# RotorStator_PowerControl.net
KiCad netlist of a schematic drawn in Altium Designer
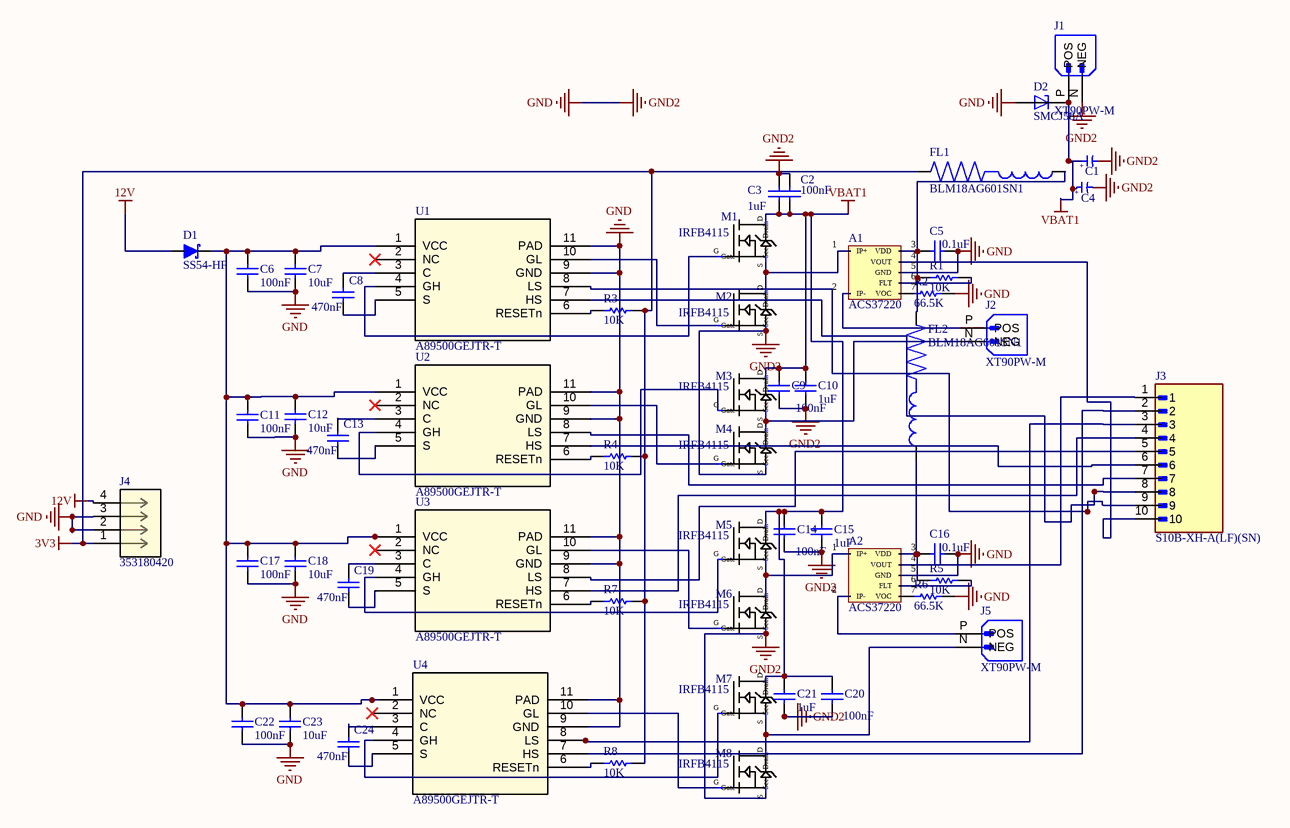
[diagram p0: RotorStator_PowerControl.SchDoc]

(export (version "E")
  (design (tool "Eeschema 10.0.6"))
  (components
    (comp (ref "A1") (value "ACS37220") (footprint "ACS37220") (libsource (lib "Schlib1") (part "ACS37220")))
    (comp (ref "A2") (value "ACS37220") (footprint "ACS37220") (libsource (lib "Schlib1") (part "ACS37220")))
    (comp (ref "C1")
      (value "MAL215099913E3")
      (footprint "CAPAE1900X2200N")
      (description "Cap Aluminum Lytic 470uF 100V 20% (18 X 21mm) SMD 1450mA 5000h 105Â°C Automotive AEC-Q200 T/R")
      (fields (field (name "MF") "Vishay Beyschlag/Draloric"))
      (libsource (lib "") (part "MAL215099913E3_1"))
    )
    (comp (ref "C2")
      (value "100nF")
      (footprint "CAP0805R")
      (description "Capacitor")
      (libsource (lib "Simulation Generic Components") (part "Capacitor"))
    )
    (comp (ref "C3")
      (value "1uF")
      (footprint "CAP0805R")
      (description "Capacitor")
      (libsource (lib "Simulation Generic Components") (part "Capacitor"))
    )
    (comp (ref "C4")
      (value "MAL215099913E3")
      (footprint "CAPAE1900X2200N")
      (description "Cap Aluminum Lytic 470uF 100V 20% (18 X 21mm) SMD 1450mA 5000h 105Â°C Automotive AEC-Q200 T/R")
      (fields (field (name "MF") "Vishay Beyschlag/Draloric"))
      (libsource (lib "Schlib1") (part "MAL215099913E3"))
    )
    (comp (ref "C5")
      (value "0.1uF")
      (footprint "CAP0805R")
      (description "Capacitor")
      (libsource (lib "Simulation Generic Components") (part "Capacitor"))
    )
    (comp (ref "C6")
      (value "100nF")
      (footprint "CAP0805R")
      (description "Capacitor")
      (libsource (lib "Simulation Generic Components") (part "Capacitor"))
    )
    (comp (ref "C7")
      (value "10uF")
      (footprint "CAP0805R")
      (description "Capacitor")
      (libsource (lib "Simulation Generic Components") (part "Capacitor"))
    )
    (comp (ref "C8")
      (value "470nF")
      (footprint "CAP0805R")
      (description "Capacitor")
      (libsource (lib "Simulation Generic Components") (part "Capacitor"))
    )
    (comp (ref "C9")
      (value "100nF")
      (footprint "CAP0805R")
      (description "Capacitor")
      (libsource (lib "Simulation Generic Components") (part "Capacitor"))
    )
    (comp (ref "C10")
      (value "1uF")
      (footprint "CAP0805R")
      (description "Capacitor")
      (libsource (lib "Simulation Generic Components") (part "Capacitor"))
    )
    (comp (ref "C11")
      (value "100nF")
      (footprint "CAP0805R")
      (description "Capacitor")
      (libsource (lib "Simulation Generic Components") (part "Capacitor"))
    )
    (comp (ref "C12")
      (value "10uF")
      (footprint "CAP0805R")
      (description "Capacitor")
      (libsource (lib "Simulation Generic Components") (part "Capacitor"))
    )
    (comp (ref "C13")
      (value "470nF")
      (footprint "CAP0805R")
      (description "Capacitor")
      (libsource (lib "Simulation Generic Components") (part "Capacitor"))
    )
    (comp (ref "C14")
      (value "100nF")
      (footprint "CAP0805R")
      (description "Capacitor")
      (libsource (lib "Simulation Generic Components") (part "Capacitor"))
    )
    (comp (ref "C15")
      (value "1uF")
      (footprint "CAP0805R")
      (description "Capacitor")
      (libsource (lib "Simulation Generic Components") (part "Capacitor"))
    )
    (comp (ref "C16")
      (value "0.1uF")
      (footprint "CAP0805R")
      (description "Capacitor")
      (libsource (lib "Simulation Generic Components") (part "Capacitor"))
    )
    (comp (ref "C17")
      (value "100nF")
      (footprint "CAP0805R")
      (description "Capacitor")
      (libsource (lib "Simulation Generic Components") (part "Capacitor"))
    )
    (comp (ref "C18")
      (value "10uF")
      (footprint "CAP0805R")
      (description "Capacitor")
      (libsource (lib "Simulation Generic Components") (part "Capacitor"))
    )
    (comp (ref "C19")
      (value "470nF")
      (footprint "CAP0805R")
      (description "Capacitor")
      (libsource (lib "Simulation Generic Components") (part "Capacitor"))
    )
    (comp (ref "C20")
      (value "100nF")
      (footprint "CAP0805R")
      (description "Capacitor")
      (libsource (lib "Simulation Generic Components") (part "Capacitor"))
    )
    (comp (ref "C21")
      (value "1uF")
      (footprint "CAP0805R")
      (description "Capacitor")
      (libsource (lib "Simulation Generic Components") (part "Capacitor"))
    )
    (comp (ref "C22")
      (value "100nF")
      (footprint "CAP0805R")
      (description "Capacitor")
      (libsource (lib "Simulation Generic Components") (part "Capacitor"))
    )
    (comp (ref "C23")
      (value "10uF")
      (footprint "CAP0805R")
      (description "Capacitor")
      (libsource (lib "Simulation Generic Components") (part "Capacitor"))
    )
    (comp (ref "C24")
      (value "470nF")
      (footprint "CAP0805R")
      (description "Capacitor")
      (libsource (lib "Simulation Generic Components") (part "Capacitor"))
    )
    (comp (ref "D1")
      (value "SS54-HF")
      (footprint "DIOM5025X220N")
      (description "Diode Schottky 40 V 5A Surface Mount DO-214AC (SMA)")
      (fields (field (name "MF") "Comchip Technology"))
      (libsource (lib "Schlib1") (part "SS54-HF"))
    )
    (comp (ref "D2")
      (value "SMCJ58A")
      (footprint "DIOM7959X262N")
      (description "93.6V Clamp 16.1A Ipp Tvs Diode Surface Mount DO-214AB (SMC)")
      (fields (field (name "MF") "Fairchild Semiconductor"))
      (libsource (lib "Schlib1") (part "SMCJ58A"))
    )
    (comp (ref "FL1")
      (value "BLM18AG601SN1")
      (footprint "BEADC1608X95N")
      (description "600 Ohms @ 100 MHz 1 - Ferrite Bead 0603 (1608 Metric) 500mA 380mOhm")
      (fields (field (name "MF") "Murata Electronics"))
      (libsource (lib "Schlib1") (part "BLM18AG601SN1"))
    )
    (comp (ref "FL2")
      (value "BLM18AG601SN1")
      (footprint "BEADC1608X95N")
      (description "600 Ohms @ 100 MHz 1 - Ferrite Bead 0603 (1608 Metric) 500mA 380mOhm")
      (fields (field (name "MF") "Murata Electronics"))
      (libsource (lib "Schlib1") (part "BLM18AG601SN1"))
    )
    (comp (ref "J1")
      (value "XT90PW-M")
      (footprint "AMASS_XT90PW-M")
      (description "Socket; DC supply; XT90; male; PIN: 2; on PCBs; THT; Colour: yellow")
      (fields (field (name "MF") "AMASS"))
      (libsource (lib "") (part "XT90PW-M_1"))
    )
    (comp (ref "J2")
      (value "XT90PW-M")
      (footprint "AMASS_XT90PW-M")
      (description "Socket; DC supply; XT90; male; PIN: 2; on PCBs; THT; Colour: yellow")
      (fields (field (name "MF") "AMASS"))
      (libsource (lib "Schlib1") (part "XT90PW-M"))
    )
    (comp (ref "J3")
      (value "S10B-XH-A(LF)(SN)")
      (footprint "JST_S10B-XH-A(LF)(SN)")
      (libsource (lib "Schlib1") (part "S10B-XH-A(LF)(SN)"))
    )
    (comp (ref "J4")
      (value "353180420")
      (footprint "MOLEX_353180420")
      (description "Connector Header Through Hole, Right Angle 4 position 0.165in (4.20mm)")
      (libsource (lib "Schlib1") (part "353180420"))
    )
    (comp (ref "J5")
      (value "XT90PW-M")
      (footprint "AMASS_XT90PW-M")
      (description "Socket; DC supply; XT90; male; PIN: 2; on PCBs; THT; Colour: yellow")
      (fields (field (name "MF") "AMASS"))
      (libsource (lib "Schlib1") (part "XT90PW-M"))
    )
    (comp (ref "M1") (value "IRFB4115") (footprint "IRFB4115") (libsource (lib "Schlib1") (part "IRFB4115")))
    (comp (ref "M2") (value "IRFB4115") (footprint "IRFB4115") (libsource (lib "Schlib1") (part "IRFB4115")))
    (comp (ref "M3") (value "IRFB4115") (footprint "IRFB4115") (libsource (lib "Schlib1") (part "IRFB4115")))
    (comp (ref "M4") (value "IRFB4115") (footprint "IRFB4115") (libsource (lib "Schlib1") (part "IRFB4115")))
    (comp (ref "M5") (value "IRFB4115") (footprint "IRFB4115") (libsource (lib "Schlib1") (part "IRFB4115")))
    (comp (ref "M6") (value "IRFB4115") (footprint "IRFB4115") (libsource (lib "Schlib1") (part "IRFB4115")))
    (comp (ref "M7") (value "IRFB4115") (footprint "IRFB4115") (libsource (lib "Schlib1") (part "IRFB4115")))
    (comp (ref "M8") (value "IRFB4115") (footprint "IRFB4115") (libsource (lib "Schlib1") (part "IRFB4115")))
    (comp (ref "R1")
      (value "10K")
      (footprint "RES0805W")
      (description "Resistor")
      (libsource (lib "Simulation Generic Components") (part "Resistor"))
    )
    (comp (ref "R2")
      (value "66.5K")
      (footprint "RES0805W")
      (description "Resistor")
      (libsource (lib "Simulation Generic Components") (part "Resistor"))
    )
    (comp (ref "R3")
      (value "10K")
      (footprint "RES0805W")
      (description "Resistor")
      (libsource (lib "Simulation Generic Components") (part "Resistor"))
    )
    (comp (ref "R4")
      (value "10K")
      (footprint "RES0805W")
      (description "Resistor")
      (libsource (lib "Simulation Generic Components") (part "Resistor"))
    )
    (comp (ref "R5")
      (value "10K")
      (footprint "RES0805W")
      (description "Resistor")
      (libsource (lib "Simulation Generic Components") (part "Resistor"))
    )
    (comp (ref "R6")
      (value "66.5K")
      (footprint "RES0805W")
      (description "Resistor")
      (libsource (lib "Simulation Generic Components") (part "Resistor"))
    )
    (comp (ref "R7")
      (value "10K")
      (footprint "RES0805W")
      (description "Resistor")
      (libsource (lib "Simulation Generic Components") (part "Resistor"))
    )
    (comp (ref "R8")
      (value "10K")
      (footprint "RES0805W")
      (description "Resistor")
      (libsource (lib "Simulation Generic Components") (part "Resistor"))
    )
    (comp (ref "U1")
      (value "A89500GEJTR-T")
      (footprint "A89500GEJTR-T")
      (description "Description")
      (fields (field (name "COPYRIGHT") "Copyright (C) 2025 Ultra Librarian. All rights reserved."))
      (libsource (lib "Schlib1") (part "A89500GEJTR-T"))
    )
    (comp (ref "U2")
      (value "A89500GEJTR-T")
      (footprint "A89500GEJTR-T")
      (description "Description")
      (fields (field (name "COPYRIGHT") "Copyright (C) 2025 Ultra Librarian. All rights reserved."))
      (libsource (lib "Schlib1") (part "A89500GEJTR-T"))
    )
    (comp (ref "U3")
      (value "A89500GEJTR-T")
      (footprint "A89500GEJTR-T")
      (description "Description")
      (fields (field (name "COPYRIGHT") "Copyright (C) 2025 Ultra Librarian. All rights reserved."))
      (libsource (lib "Schlib1") (part "A89500GEJTR-T"))
    )
    (comp (ref "U4")
      (value "A89500GEJTR-T")
      (footprint "A89500GEJTR-T")
      (description "Description")
      (fields (field (name "COPYRIGHT") "Copyright (C) 2025 Ultra Librarian. All rights reserved."))
      (libsource (lib "Schlib1") (part "A89500GEJTR-T"))
    )
  )
  (nets
    (net (code "1") (name "3V3") (class "Default")
      (node (ref "FL1") (pin "2") (pinfunction "2_2") (pintype "passive"))
      (node (ref "J4") (pin "1") (pinfunction "1_1") (pintype "passive"))
      (node (ref "R3") (pin "1") (pinfunction "1_1") (pintype "passive"))
      (node (ref "R4") (pin "1") (pinfunction "1_1") (pintype "passive"))
      (node (ref "R7") (pin "1") (pinfunction "1_1") (pintype "passive"))
      (node (ref "R8") (pin "1") (pinfunction "1_1") (pintype "passive"))
    )
    (net (code "2") (name "12V") (class "Default")
      (node (ref "D1") (pin "2") (pinfunction "A_2") (pintype "bidirectional"))
      (node (ref "J4") (pin "4") (pinfunction "4_4") (pintype "passive"))
    )
    (net (code "3") (name "GND") (class "Default")
      (node (ref "A1") (pin "5") (pinfunction "GND_5") (pintype "passive"))
      (node (ref "A2") (pin "5") (pinfunction "GND_5") (pintype "passive"))
      (node (ref "C1") (pin "2") (pinfunction "2_2") (pintype "passive"))
      (node (ref "C10") (pin "2") (pinfunction "2_2") (pintype "passive"))
      (node (ref "C11") (pin "2") (pinfunction "2_2") (pintype "passive"))
      (node (ref "C12") (pin "2") (pinfunction "2_2") (pintype "passive"))
      (node (ref "C14") (pin "2") (pinfunction "2_2") (pintype "passive"))
      (node (ref "C15") (pin "2") (pinfunction "2_2") (pintype "passive"))
      (node (ref "C16") (pin "2") (pinfunction "2_2") (pintype "passive"))
      (node (ref "C17") (pin "2") (pinfunction "2_2") (pintype "passive"))
      (node (ref "C18") (pin "2") (pinfunction "2_2") (pintype "passive"))
      (node (ref "C2") (pin "2") (pinfunction "2_2") (pintype "passive"))
      (node (ref "C20") (pin "2") (pinfunction "2_2") (pintype "passive"))
      (node (ref "C21") (pin "2") (pinfunction "2_2") (pintype "passive"))
      (node (ref "C22") (pin "2") (pinfunction "2_2") (pintype "passive"))
      (node (ref "C23") (pin "2") (pinfunction "2_2") (pintype "passive"))
      (node (ref "C3") (pin "2") (pinfunction "2_2") (pintype "passive"))
      (node (ref "C4") (pin "2") (pinfunction "2_2") (pintype "passive"))
      (node (ref "C5") (pin "2") (pinfunction "2_2") (pintype "passive"))
      (node (ref "C6") (pin "2") (pinfunction "2_2") (pintype "passive"))
      (node (ref "C7") (pin "2") (pinfunction "2_2") (pintype "passive"))
      (node (ref "C9") (pin "2") (pinfunction "2_2") (pintype "passive"))
      (node (ref "D2") (pin "A") (pinfunction "A_A") (pintype "passive"))
      (node (ref "J1") (pin "N") (pinfunction "NEG_N") (pintype "passive"))
      (node (ref "J4") (pin "2") (pinfunction "2_2") (pintype "passive"))
      (node (ref "J4") (pin "3") (pinfunction "3_3") (pintype "passive"))
      (node (ref "M2") (pin "S") (pinfunction "Sce_S") (pintype "passive"))
      (node (ref "M4") (pin "S") (pinfunction "Sce_S") (pintype "passive"))
      (node (ref "M6") (pin "S") (pinfunction "Sce_S") (pintype "passive"))
      (node (ref "M8") (pin "S") (pinfunction "Sce_S") (pintype "passive"))
      (node (ref "R2") (pin "2") (pinfunction "2_2") (pintype "passive"))
      (node (ref "R6") (pin "2") (pinfunction "2_2") (pintype "passive"))
      (node (ref "U1") (pin "11") (pinfunction "PAD_11") (pintype "passive"))
      (node (ref "U1") (pin "9") (pinfunction "GND_9") (pintype "power_in"))
      (node (ref "U2") (pin "11") (pinfunction "PAD_11") (pintype "passive"))
      (node (ref "U2") (pin "9") (pinfunction "GND_9") (pintype "power_in"))
      (node (ref "U3") (pin "11") (pinfunction "PAD_11") (pintype "passive"))
      (node (ref "U3") (pin "9") (pinfunction "GND_9") (pintype "power_in"))
      (node (ref "U4") (pin "11") (pinfunction "PAD_11") (pintype "passive"))
      (node (ref "U4") (pin "9") (pinfunction "GND_9") (pintype "power_in"))
    )
    (net (code "4") (name "Net-(A1-FLT)") (class "Default")
      (node (ref "A1") (pin "6") (pinfunction "FLT_6") (pintype "passive"))
      (node (ref "R1") (pin "2") (pinfunction "2_2") (pintype "passive"))
    )
    (net (code "5") (name "Net-(A1-IP+)") (class "Default")
      (node (ref "A1") (pin "1") (pinfunction "IP+_1") (pintype "passive"))
      (node (ref "M1") (pin "S") (pinfunction "Sce_S") (pintype "passive"))
      (node (ref "M2") (pin "D") (pinfunction "Drain_D") (pintype "passive"))
    )
    (net (code "6") (name "Net-(A1-IP-)") (class "Default")
      (node (ref "A1") (pin "2") (pinfunction "IP-_2") (pintype "passive"))
      (node (ref "J2") (pin "P") (pinfunction "POS_P") (pintype "passive"))
    )
    (net (code "7") (name "Net-(A1-VDD)") (class "Default")
      (node (ref "A1") (pin "3") (pinfunction "VDD_3") (pintype "power_in"))
      (node (ref "C5") (pin "1") (pinfunction "1_1") (pintype "passive"))
      (node (ref "FL1") (pin "1") (pinfunction "1_1") (pintype "passive"))
      (node (ref "FL2") (pin "2") (pinfunction "2_2") (pintype "passive"))
      (node (ref "R1") (pin "1") (pinfunction "1_1") (pintype "passive"))
    )
    (net (code "8") (name "Net-(A1-VOC)") (class "Default")
      (node (ref "A1") (pin "7") (pinfunction "VOC_7") (pintype "passive"))
      (node (ref "R2") (pin "1") (pinfunction "1_1") (pintype "passive"))
    )
    (net (code "9") (name "Net-(A1-VOUT)") (class "Default")
      (node (ref "A1") (pin "4") (pinfunction "VOUT_4") (pintype "passive"))
      (node (ref "J3") (pin "10") (pinfunction "10_10") (pintype "passive"))
    )
    (net (code "10") (name "Net-(A2-FLT)") (class "Default")
      (node (ref "A2") (pin "6") (pinfunction "FLT_6") (pintype "passive"))
      (node (ref "R5") (pin "2") (pinfunction "2_2") (pintype "passive"))
    )
    (net (code "11") (name "Net-(A2-IP+)") (class "Default")
      (node (ref "A2") (pin "1") (pinfunction "IP+_1") (pintype "passive"))
      (node (ref "M5") (pin "S") (pinfunction "Sce_S") (pintype "passive"))
      (node (ref "M6") (pin "D") (pinfunction "Drain_D") (pintype "passive"))
    )
    (net (code "12") (name "Net-(A2-IP-)") (class "Default")
      (node (ref "A2") (pin "2") (pinfunction "IP-_2") (pintype "passive"))
      (node (ref "J5") (pin "P") (pinfunction "POS_P") (pintype "passive"))
    )
    (net (code "13") (name "Net-(A2-VDD)") (class "Default")
      (node (ref "A2") (pin "3") (pinfunction "VDD_3") (pintype "power_in"))
      (node (ref "C16") (pin "1") (pinfunction "1_1") (pintype "passive"))
      (node (ref "FL2") (pin "1") (pinfunction "1_1") (pintype "passive"))
      (node (ref "R5") (pin "1") (pinfunction "1_1") (pintype "passive"))
    )
    (net (code "14") (name "Net-(A2-VOC)") (class "Default")
      (node (ref "A2") (pin "7") (pinfunction "VOC_7") (pintype "passive"))
      (node (ref "R6") (pin "1") (pinfunction "1_1") (pintype "passive"))
    )
    (net (code "15") (name "Net-(A2-VOUT)") (class "Default")
      (node (ref "A2") (pin "4") (pinfunction "VOUT_4") (pintype "passive"))
      (node (ref "J3") (pin "1") (pinfunction "1_1") (pintype "passive"))
    )
    (net (code "16") (name "Net-(D1-K)") (class "Default")
      (node (ref "C11") (pin "1") (pinfunction "1_1") (pintype "passive"))
      (node (ref "C12") (pin "1") (pinfunction "1_1") (pintype "passive"))
      (node (ref "C17") (pin "1") (pinfunction "1_1") (pintype "passive"))
      (node (ref "C18") (pin "1") (pinfunction "1_1") (pintype "passive"))
      (node (ref "C22") (pin "1") (pinfunction "1_1") (pintype "passive"))
      (node (ref "C23") (pin "1") (pinfunction "1_1") (pintype "passive"))
      (node (ref "C6") (pin "1") (pinfunction "1_1") (pintype "passive"))
      (node (ref "C7") (pin "1") (pinfunction "1_1") (pintype "passive"))
      (node (ref "D1") (pin "1") (pinfunction "K_1") (pintype "bidirectional"))
      (node (ref "U1") (pin "1") (pinfunction "VCC_1") (pintype "power_in"))
      (node (ref "U2") (pin "1") (pinfunction "VCC_1") (pintype "power_in"))
      (node (ref "U3") (pin "1") (pinfunction "VCC_1") (pintype "power_in"))
      (node (ref "U4") (pin "1") (pinfunction "VCC_1") (pintype "power_in"))
    )
    (net (code "17") (name "Net-(J2-NEG)") (class "Default")
      (node (ref "J2") (pin "N") (pinfunction "NEG_N") (pintype "passive"))
      (node (ref "M3") (pin "S") (pinfunction "Sce_S") (pintype "passive"))
      (node (ref "M4") (pin "D") (pinfunction "Drain_D") (pintype "passive"))
    )
    (net (code "18") (name "Net-(J5-NEG)") (class "Default")
      (node (ref "J5") (pin "N") (pinfunction "NEG_N") (pintype "passive"))
      (node (ref "M7") (pin "S") (pinfunction "Sce_S") (pintype "passive"))
      (node (ref "M8") (pin "D") (pinfunction "Drain_D") (pintype "passive"))
    )
    (net (code "19") (name "Net-(M1-Gate)") (class "Default")
      (node (ref "M1") (pin "G") (pinfunction "Gate_G") (pintype "passive"))
      (node (ref "U1") (pin "4") (pinfunction "GH_4") (pintype "passive"))
    )
    (net (code "20") (name "Net-(M2-Gate)") (class "Default")
      (node (ref "M2") (pin "G") (pinfunction "Gate_G") (pintype "passive"))
      (node (ref "U1") (pin "10") (pinfunction "GL_10") (pintype "passive"))
    )
    (net (code "21") (name "Net-(M3-Gate)") (class "Default")
      (node (ref "M3") (pin "G") (pinfunction "Gate_G") (pintype "passive"))
      (node (ref "U2") (pin "4") (pinfunction "GH_4") (pintype "passive"))
    )
    (net (code "22") (name "Net-(M4-Gate)") (class "Default")
      (node (ref "M4") (pin "G") (pinfunction "Gate_G") (pintype "passive"))
      (node (ref "U2") (pin "10") (pinfunction "GL_10") (pintype "passive"))
    )
    (net (code "23") (name "Net-(M5-Gate)") (class "Default")
      (node (ref "M5") (pin "G") (pinfunction "Gate_G") (pintype "passive"))
      (node (ref "U3") (pin "4") (pinfunction "GH_4") (pintype "passive"))
    )
    (net (code "24") (name "Net-(M6-Gate)") (class "Default")
      (node (ref "M6") (pin "G") (pinfunction "Gate_G") (pintype "passive"))
      (node (ref "U3") (pin "10") (pinfunction "GL_10") (pintype "passive"))
    )
    (net (code "25") (name "Net-(M7-Gate)") (class "Default")
      (node (ref "M7") (pin "G") (pinfunction "Gate_G") (pintype "passive"))
      (node (ref "U4") (pin "4") (pinfunction "GH_4") (pintype "passive"))
    )
    (net (code "26") (name "Net-(M8-Gate)") (class "Default")
      (node (ref "M8") (pin "G") (pinfunction "Gate_G") (pintype "passive"))
      (node (ref "U4") (pin "10") (pinfunction "GL_10") (pintype "passive"))
    )
    (net (code "27") (name "Net-(U1-C)") (class "Default")
      (node (ref "C8") (pin "1") (pinfunction "1_1") (pintype "passive"))
      (node (ref "U1") (pin "3") (pinfunction "C_3") (pintype "passive"))
    )
    (net (code "28") (name "Net-(U1-HS)") (class "Default")
      (node (ref "J3") (pin "8") (pinfunction "8_8") (pintype "passive"))
      (node (ref "U1") (pin "7") (pinfunction "HS_7") (pintype "passive"))
    )
    (net (code "29") (name "Net-(U1-LS)") (class "Default")
      (node (ref "J3") (pin "9") (pinfunction "9_9") (pintype "passive"))
      (node (ref "U1") (pin "8") (pinfunction "LS_8") (pintype "passive"))
    )
    (net (code "30") (name "Net-(U1-RESETn)") (class "Default")
      (node (ref "R3") (pin "2") (pinfunction "2_2") (pintype "passive"))
      (node (ref "U1") (pin "6") (pinfunction "RESETn_6") (pintype "passive"))
    )
    (net (code "31") (name "Net-(U1-S)") (class "Default")
      (node (ref "C8") (pin "2") (pinfunction "2_2") (pintype "passive"))
      (node (ref "U1") (pin "5") (pinfunction "S_5") (pintype "passive"))
    )
    (net (code "32") (name "Net-(U2-C)") (class "Default")
      (node (ref "C13") (pin "1") (pinfunction "1_1") (pintype "passive"))
      (node (ref "U2") (pin "3") (pinfunction "C_3") (pintype "passive"))
    )
    (net (code "33") (name "Net-(U2-HS)") (class "Default")
      (node (ref "J3") (pin "6") (pinfunction "6_6") (pintype "passive"))
      (node (ref "U2") (pin "7") (pinfunction "HS_7") (pintype "passive"))
    )
    (net (code "34") (name "Net-(U2-LS)") (class "Default")
      (node (ref "J3") (pin "7") (pinfunction "7_7") (pintype "passive"))
      (node (ref "U2") (pin "8") (pinfunction "LS_8") (pintype "passive"))
    )
    (net (code "35") (name "Net-(U2-RESETn)") (class "Default")
      (node (ref "R4") (pin "2") (pinfunction "2_2") (pintype "passive"))
      (node (ref "U2") (pin "6") (pinfunction "RESETn_6") (pintype "passive"))
    )
    (net (code "36") (name "Net-(U2-S)") (class "Default")
      (node (ref "C13") (pin "2") (pinfunction "2_2") (pintype "passive"))
      (node (ref "U2") (pin "5") (pinfunction "S_5") (pintype "passive"))
    )
    (net (code "37") (name "Net-(U3-C)") (class "Default")
      (node (ref "C19") (pin "1") (pinfunction "1_1") (pintype "passive"))
      (node (ref "U3") (pin "3") (pinfunction "C_3") (pintype "passive"))
    )
    (net (code "38") (name "Net-(U3-HS)") (class "Default")
      (node (ref "J3") (pin "4") (pinfunction "4_4") (pintype "passive"))
      (node (ref "U3") (pin "7") (pinfunction "HS_7") (pintype "passive"))
    )
    (net (code "39") (name "Net-(U3-LS)") (class "Default")
      (node (ref "J3") (pin "5") (pinfunction "5_5") (pintype "passive"))
      (node (ref "U3") (pin "8") (pinfunction "LS_8") (pintype "passive"))
    )
    (net (code "40") (name "Net-(U3-RESETn)") (class "Default")
      (node (ref "R7") (pin "2") (pinfunction "2_2") (pintype "passive"))
      (node (ref "U3") (pin "6") (pinfunction "RESETn_6") (pintype "passive"))
    )
    (net (code "41") (name "Net-(U3-S)") (class "Default")
      (node (ref "C19") (pin "2") (pinfunction "2_2") (pintype "passive"))
      (node (ref "U3") (pin "5") (pinfunction "S_5") (pintype "passive"))
    )
    (net (code "42") (name "Net-(U4-C)") (class "Default")
      (node (ref "C24") (pin "1") (pinfunction "1_1") (pintype "passive"))
      (node (ref "U4") (pin "3") (pinfunction "C_3") (pintype "passive"))
    )
    (net (code "43") (name "Net-(U4-HS)") (class "Default")
      (node (ref "J3") (pin "2") (pinfunction "2_2") (pintype "passive"))
      (node (ref "U4") (pin "7") (pinfunction "HS_7") (pintype "passive"))
    )
    (net (code "44") (name "Net-(U4-LS)") (class "Default")
      (node (ref "J3") (pin "3") (pinfunction "3_3") (pintype "passive"))
      (node (ref "U4") (pin "8") (pinfunction "LS_8") (pintype "passive"))
    )
    (net (code "45") (name "Net-(U4-RESETn)") (class "Default")
      (node (ref "R8") (pin "2") (pinfunction "2_2") (pintype "passive"))
      (node (ref "U4") (pin "6") (pinfunction "RESETn_6") (pintype "passive"))
    )
    (net (code "46") (name "Net-(U4-S)") (class "Default")
      (node (ref "C24") (pin "2") (pinfunction "2_2") (pintype "passive"))
      (node (ref "U4") (pin "5") (pinfunction "S_5") (pintype "passive"))
    )
    (net (code "47") (name "VBAT1") (class "Default")
      (node (ref "C1") (pin "1") (pinfunction "1_1") (pintype "passive"))
      (node (ref "C10") (pin "1") (pinfunction "1_1") (pintype "passive"))
      (node (ref "C14") (pin "1") (pinfunction "1_1") (pintype "passive"))
      (node (ref "C15") (pin "1") (pinfunction "1_1") (pintype "passive"))
      (node (ref "C2") (pin "1") (pinfunction "1_1") (pintype "passive"))
      (node (ref "C20") (pin "1") (pinfunction "1_1") (pintype "passive"))
      (node (ref "C21") (pin "1") (pinfunction "1_1") (pintype "passive"))
      (node (ref "C3") (pin "1") (pinfunction "1_1") (pintype "passive"))
      (node (ref "C4") (pin "1") (pinfunction "1_1") (pintype "passive"))
      (node (ref "C9") (pin "1") (pinfunction "1_1") (pintype "passive"))
      (node (ref "D2") (pin "C") (pinfunction "C_C") (pintype "passive"))
      (node (ref "J1") (pin "P") (pinfunction "POS_P") (pintype "passive"))
      (node (ref "M1") (pin "D") (pinfunction "Drain_D") (pintype "passive"))
      (node (ref "M3") (pin "D") (pinfunction "Drain_D") (pintype "passive"))
      (node (ref "M5") (pin "D") (pinfunction "Drain_D") (pintype "passive"))
      (node (ref "M7") (pin "D") (pinfunction "Drain_D") (pintype "passive"))
    )
    (net (code "48") (name "unconnected-(U1-NC-Pad2)") (class "Default")
      (node (ref "U1") (pin "2") (pinfunction "NC_2") (pintype "passive+no_connect"))
    )
    (net (code "49") (name "unconnected-(U2-NC-Pad2)") (class "Default")
      (node (ref "U2") (pin "2") (pinfunction "NC_2") (pintype "passive+no_connect"))
    )
    (net (code "50") (name "unconnected-(U3-NC-Pad2)") (class "Default")
      (node (ref "U3") (pin "2") (pinfunction "NC_2") (pintype "passive+no_connect"))
    )
    (net (code "51") (name "unconnected-(U4-NC-Pad2)") (class "Default")
      (node (ref "U4") (pin "2") (pinfunction "NC_2") (pintype "passive+no_connect"))
    )
  )
)
